# C8T6.net
KiCad netlist of a schematic drawn in Altium Designer
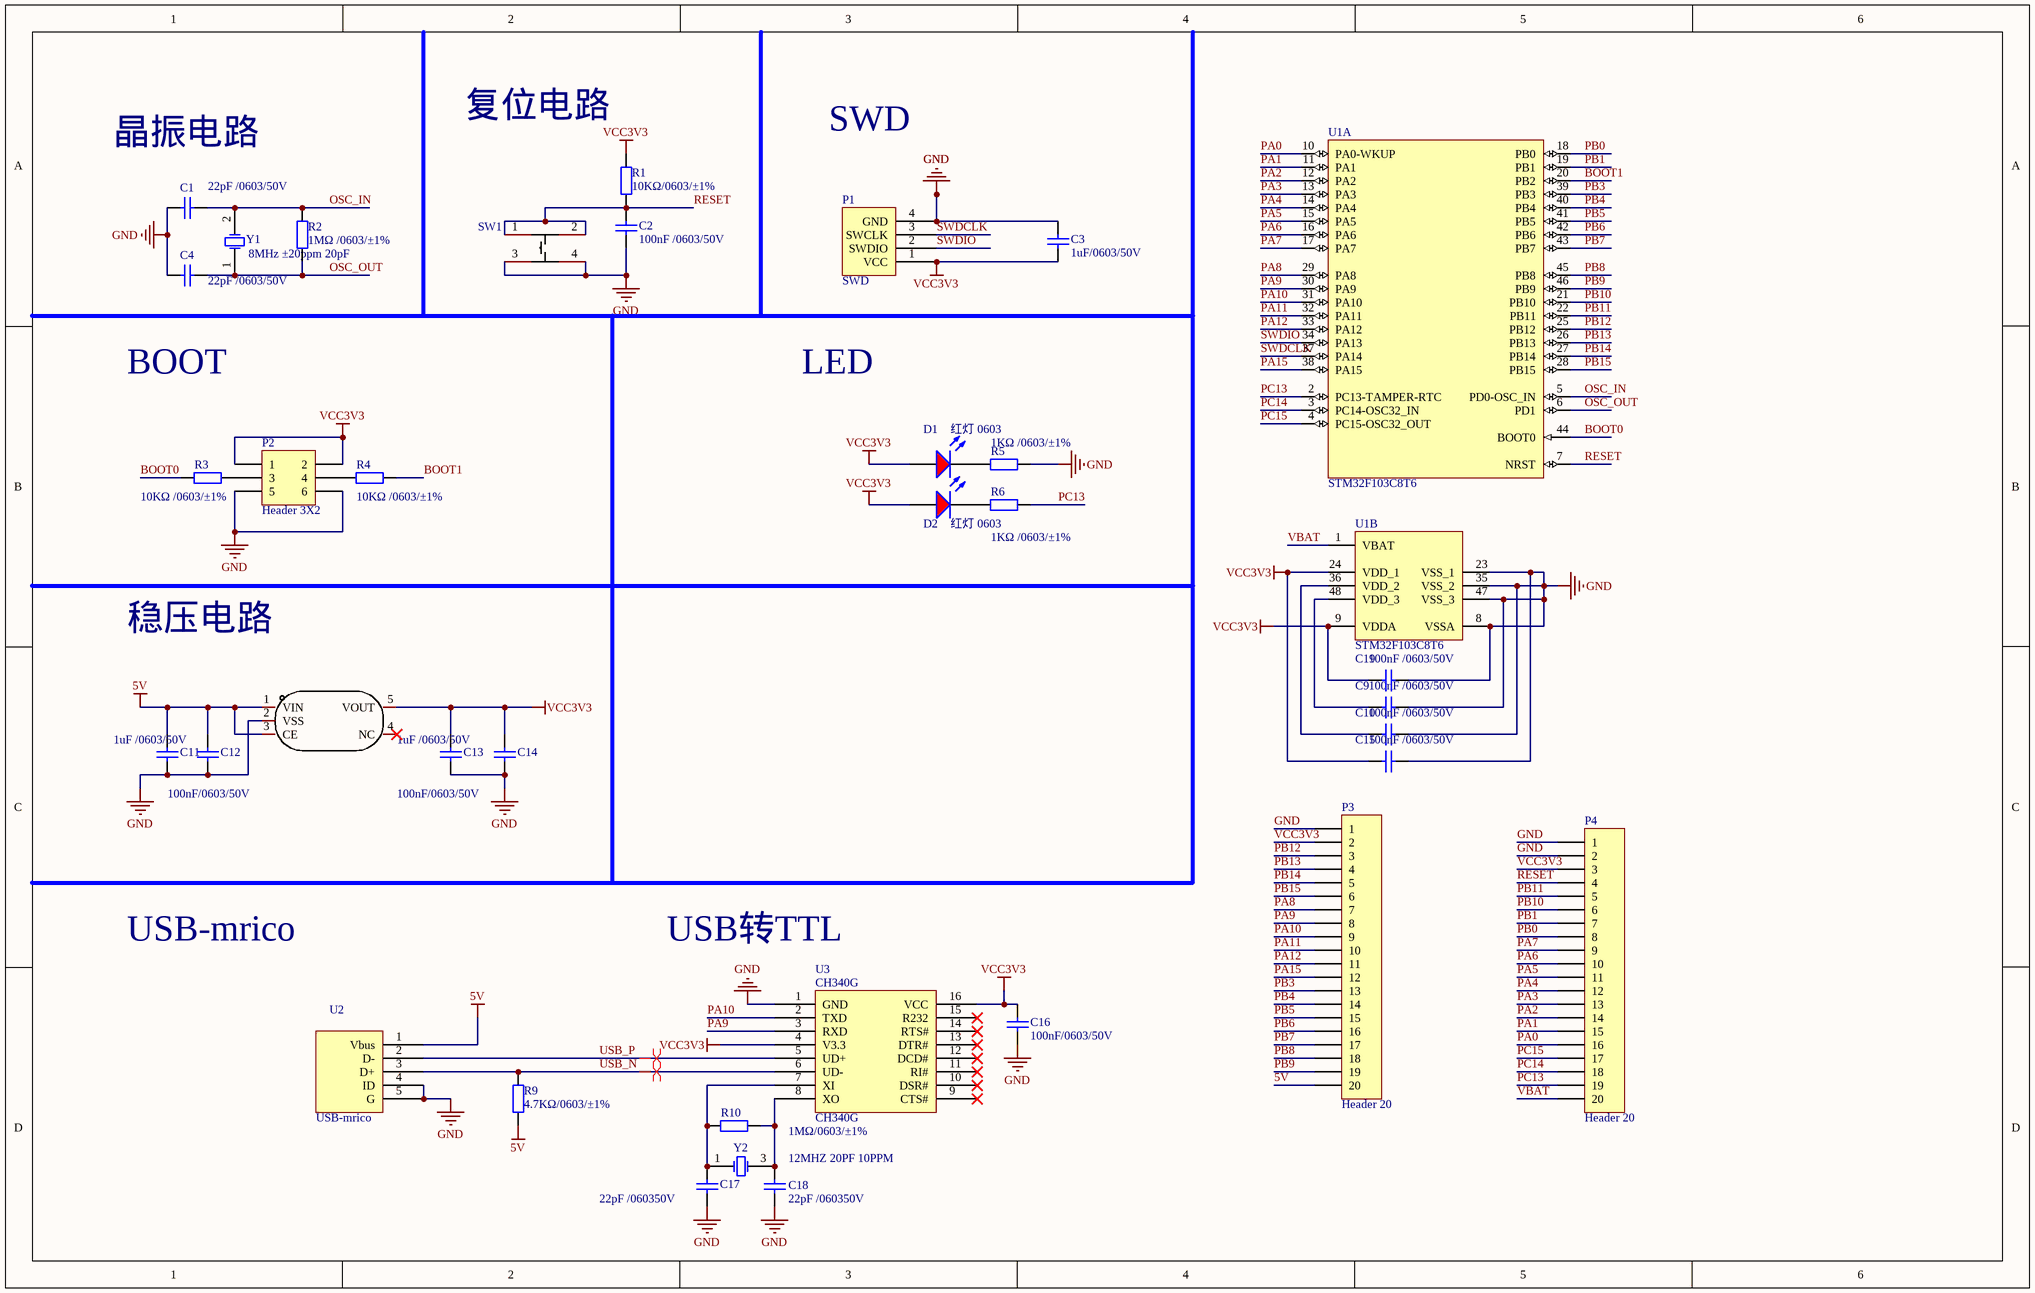
[diagram p0: C8T6.SchDoc]

(export (version "E")
  (design (tool "Eeschema 10.0.6"))
  (components
    (comp (ref "C1")
      (value "22pF /0603/50V")
      (footprint "0603_C")
      (description "贴片电容")
      (libsource (lib "C8T6") (part "0603 22pF (220) 5% 50V"))
    )
    (comp (ref "C2")
      (value "100nF /0603/50V")
      (footprint "0603_C")
      (description "贴片电容")
      (libsource (lib "C8T6") (part "0603 100nF (104) 10% 50V"))
    )
    (comp (ref "C3")
      (value "1uF/0603/50V")
      (footprint "0603_C")
      (description "贴片电容")
      (libsource (lib "C8T6") (part "0603 1uF (105) 10% 50V"))
    )
    (comp (ref "C4")
      (value "22pF /0603/50V")
      (footprint "0603_C")
      (description "贴片电容")
      (libsource (lib "C8T6") (part "0603 22pF (220) 5% 50V"))
    )
    (comp (ref "C9")
      (value "100nF /0603/50V")
      (footprint "0603_C")
      (description "贴片电容")
      (libsource (lib "C8T6") (part "0603 100nF (104) 10% 50V"))
    )
    (comp (ref "C10")
      (value "100nF /0603/50V")
      (footprint "0603_C")
      (description "贴片电容")
      (libsource (lib "C8T6") (part "0603 100nF (104) 10% 50V"))
    )
    (comp (ref "C11")
      (value "1uF /0603/50V")
      (footprint "0603_C")
      (description "贴片电容")
      (libsource (lib "C8T6") (part "0603 1uF (105) 10% 50V"))
    )
    (comp (ref "C12")
      (value "100nF/0603/50V")
      (footprint "0603_C")
      (description "贴片电容")
      (libsource (lib "C8T6") (part "0603 100nF (104) 10% 50V"))
    )
    (comp (ref "C13")
      (value "1uF /0603/50V")
      (footprint "0603_C")
      (description "贴片电容")
      (libsource (lib "C8T6") (part "0603 1uF (105) 10% 50V"))
    )
    (comp (ref "C14")
      (value "100nF/0603/50V")
      (footprint "0603_C")
      (description "贴片电容")
      (libsource (lib "C8T6") (part "0603 100nF (104) 10% 50V"))
    )
    (comp (ref "C15")
      (value "100nF /0603/50V")
      (footprint "0603_C")
      (description "贴片电容")
      (libsource (lib "C8T6") (part "0603 100nF (104) 10% 50V"))
    )
    (comp (ref "C16")
      (value "100nF/0603/50V")
      (footprint "0603_C")
      (description "贴片电容")
      (libsource (lib "C8T6") (part "0603 100nF (104) 10% 50V"))
    )
    (comp (ref "C17")
      (value "22pF /060350V")
      (footprint "0603_C")
      (description "贴片电容")
      (libsource (lib "C8T6") (part "0603 22pF (220) 5% 50V"))
    )
    (comp (ref "C18")
      (value "22pF /060350V")
      (footprint "0603_C")
      (description "贴片电容")
      (libsource (lib "C8T6") (part "0603 22pF (220) 5% 50V"))
    )
    (comp (ref "C19")
      (value "100nF /0603/50V")
      (footprint "0603_C")
      (description "贴片电容")
      (libsource (lib "C8T6") (part "0603 100nF (104) 10% 50V"))
    )
    (comp (ref "D1")
      (value "红灯 0603")
      (footprint "0603_LED_S1")
      (description "发光二极管")
      (libsource (lib "C8T6") (part "0603 红灯"))
    )
    (comp (ref "D2")
      (value "红灯 0603")
      (footprint "0603_LED_S1")
      (description "发光二极管")
      (libsource (lib "C8T6") (part "0603 红灯"))
    )
    (comp (ref "LDO1")
      (value "ME6211C33M5G-N")
      (footprint "SOT-23-5_L3.0-W1.7-P0.95-LS2.8-BL")
      (fields (field (name "MANUFACTURER") "MICRONE(南京微盟)"))
      (libsource (lib "altium-import") (part "root_0_ME6211C33M5G-N_"))
    )
    (comp (ref "P1") (value "SWD") (footprint "HDR4x1") (libsource (lib "系统板原理图库") (part "SWD")))
    (comp (ref "P2")
      (value "Header 3X2")
      (footprint "HDR2X3")
      (description "Header, 3-Pin, Dual row")
      (fields (field (name "PUBLISHER") "Altium Limited"))
      (libsource (lib "系统板原理图库") (part "Header 3X2"))
    )
    (comp (ref "P3")
      (value "Header 20")
      (footprint "HDR1X20")
      (description "Header, 20-Pin")
      (fields (field (name "PUBLISHER") "Altium Limited"))
      (libsource (lib "C8T6") (part "Header 20"))
    )
    (comp (ref "P4")
      (value "Header 20")
      (footprint "HDR1X20")
      (description "Header, 20-Pin")
      (fields (field (name "PUBLISHER") "Altium Limited"))
      (libsource (lib "C8T6") (part "Header 20"))
    )
    (comp (ref "R1")
      (value "10KΩ/0603/±1%")
      (footprint "0603_R")
      (description "贴片电阻")
      (libsource (lib "C8T6") (part "0603 10KΩ (1002) 1%_1"))
    )
    (comp (ref "R2")
      (value "1MΩ /0603/±1%")
      (footprint "0603_R")
      (description "贴片电阻")
      (libsource (lib "") (part "0603 1MΩ (1004) 1%_1"))
    )
    (comp (ref "R3")
      (value "10KΩ /0603/±1%")
      (footprint "0603_R")
      (description "贴片电阻")
      (libsource (lib "") (part "0603 10KΩ (1002) 1%_1_1"))
    )
    (comp (ref "R4")
      (value "10KΩ /0603/±1%")
      (footprint "0603_R")
      (description "贴片电阻")
      (libsource (lib "") (part "0603 10KΩ (1002) 1%_1_1"))
    )
    (comp (ref "R5")
      (value "1KΩ /0603/±1%")
      (footprint "0603_R")
      (description "贴片电阻")
      (libsource (lib "") (part "0603 10KΩ (1002) 1%_1_1"))
    )
    (comp (ref "R6")
      (value "1KΩ /0603/±1%")
      (footprint "0603_R")
      (description "贴片电阻")
      (libsource (lib "") (part "0603 10KΩ (1002) 1%_1_1"))
    )
    (comp (ref "R9")
      (value "4.7KΩ/0603/±1%")
      (footprint "0603_R")
      (description "贴片电阻")
      (libsource (lib "C8T6") (part "0603 4.7KΩ (4701) 1%"))
    )
    (comp (ref "R10")
      (value "1MΩ/0603/±1%")
      (footprint "0603_R")
      (description "贴片电阻")
      (libsource (lib "C8T6") (part "0603 1MΩ (1004) 1%"))
    )
    (comp (ref "SW1")
      (value "KEY_SMD_4P")
      (footprint "SW-SMD_4P-L4.2-W3.3-P2.15-LS5.1 - duplicate")
      (libsource (lib "系统板原理图库") (part "KEY_SMD_4P"))
    )
    (comp (ref "U1")
      (value "STM32F103C8T6")
      (footprint "LQFP-48_7x7x05P")
      (description "ARM")
      (libsource (lib "C8T6") (part "STM32F103C8T6"))
    )
    (comp (ref "U2") (value "USB-mrico") (footprint "Micro_USB") (libsource (lib "系统板原理图库") (part "usb-STM")))
    (comp (ref "U3")
      (value "CH340G")
      (footprint "SOIC-16_150mil")
      (description "USB")
      (libsource (lib "C8T6") (part "CH340G_[C14267]"))
    )
    (comp (ref "Y1")
      (value "8MHz ±20ppm 20pF")
      (footprint "SMD-5032_2P")
      (description "贴片晶振")
      (libsource (lib "C8T6") (part "SMD-5032_2P 8MHz 20ppm 20pF"))
    )
    (comp (ref "Y2")
      (value "12MHZ 20PF 10PPM")
      (footprint "SMD-3225_4P")
      (description "贴片晶振")
      (libsource (lib "C8T6") (part "SMD-3225_4P  12MHZ 20PF 10PPM"))
    )
  )
  (nets
    (net (code "1") (name "/BOOT0") (class "Default")
      (node (ref "R3") (pin "1") (pinfunction "1_1") (pintype "passive"))
      (node (ref "U1") (pin "44") (pinfunction "BOOT0_44") (pintype "input"))
    )
    (net (code "2") (name "/BOOT1") (class "Default")
      (node (ref "R4") (pin "2") (pinfunction "2_2") (pintype "passive"))
      (node (ref "U1") (pin "20") (pinfunction "PB2_20") (pintype "bidirectional"))
    )
    (net (code "3") (name "/OSC_IN") (class "Default")
      (node (ref "C1") (pin "2") (pinfunction "2_2") (pintype "passive"))
      (node (ref "R2") (pin "2") (pinfunction "2_2") (pintype "passive"))
      (node (ref "U1") (pin "5") (pinfunction "PD0-OSC_IN_5") (pintype "bidirectional"))
      (node (ref "Y1") (pin "2") (pinfunction "OSC2_2") (pintype "passive"))
    )
    (net (code "4") (name "/OSC_OUT") (class "Default")
      (node (ref "C4") (pin "2") (pinfunction "2_2") (pintype "passive"))
      (node (ref "R2") (pin "1") (pinfunction "1_1") (pintype "passive"))
      (node (ref "U1") (pin "6") (pinfunction "PD1_6") (pintype "bidirectional"))
      (node (ref "Y1") (pin "1") (pinfunction "OSC1_1") (pintype "passive"))
    )
    (net (code "5") (name "/PA0") (class "Default")
      (node (ref "P4") (pin "16") (pinfunction "16_16") (pintype "passive"))
      (node (ref "U1") (pin "10") (pinfunction "PA0-WKUP_10") (pintype "bidirectional"))
    )
    (net (code "6") (name "/PA1") (class "Default")
      (node (ref "P4") (pin "15") (pinfunction "15_15") (pintype "passive"))
      (node (ref "U1") (pin "11") (pinfunction "PA1_11") (pintype "bidirectional"))
    )
    (net (code "7") (name "/PA2") (class "Default")
      (node (ref "P4") (pin "14") (pinfunction "14_14") (pintype "passive"))
      (node (ref "U1") (pin "12") (pinfunction "PA2_12") (pintype "bidirectional"))
    )
    (net (code "8") (name "/PA3") (class "Default")
      (node (ref "P4") (pin "13") (pinfunction "13_13") (pintype "passive"))
      (node (ref "U1") (pin "13") (pinfunction "PA3_13") (pintype "bidirectional"))
    )
    (net (code "9") (name "/PA4") (class "Default")
      (node (ref "P4") (pin "12") (pinfunction "12_12") (pintype "passive"))
      (node (ref "U1") (pin "14") (pinfunction "PA4_14") (pintype "bidirectional"))
    )
    (net (code "10") (name "/PA5") (class "Default")
      (node (ref "P4") (pin "11") (pinfunction "11_11") (pintype "passive"))
      (node (ref "U1") (pin "15") (pinfunction "PA5_15") (pintype "bidirectional"))
    )
    (net (code "11") (name "/PA6") (class "Default")
      (node (ref "P4") (pin "10") (pinfunction "10_10") (pintype "passive"))
      (node (ref "U1") (pin "16") (pinfunction "PA6_16") (pintype "bidirectional"))
    )
    (net (code "12") (name "/PA7") (class "Default")
      (node (ref "P4") (pin "9") (pinfunction "9_9") (pintype "passive"))
      (node (ref "U1") (pin "17") (pinfunction "PA7_17") (pintype "bidirectional"))
    )
    (net (code "13") (name "/PA8") (class "Default")
      (node (ref "P3") (pin "7") (pinfunction "7_7") (pintype "passive"))
      (node (ref "U1") (pin "29") (pinfunction "PA8_29") (pintype "bidirectional"))
    )
    (net (code "14") (name "/PA9") (class "Default")
      (node (ref "P3") (pin "8") (pinfunction "8_8") (pintype "passive"))
      (node (ref "U1") (pin "30") (pinfunction "PA9_30") (pintype "bidirectional"))
      (node (ref "U3") (pin "3") (pinfunction "RXD_3") (pintype "passive"))
    )
    (net (code "15") (name "/PA10") (class "Default")
      (node (ref "P3") (pin "9") (pinfunction "9_9") (pintype "passive"))
      (node (ref "U1") (pin "31") (pinfunction "PA10_31") (pintype "bidirectional"))
      (node (ref "U3") (pin "2") (pinfunction "TXD_2") (pintype "passive"))
    )
    (net (code "16") (name "/PA11") (class "Default")
      (node (ref "P3") (pin "10") (pinfunction "10_10") (pintype "passive"))
      (node (ref "U1") (pin "32") (pinfunction "PA11_32") (pintype "bidirectional"))
    )
    (net (code "17") (name "/PA12") (class "Default")
      (node (ref "P3") (pin "11") (pinfunction "11_11") (pintype "passive"))
      (node (ref "U1") (pin "33") (pinfunction "PA12_33") (pintype "bidirectional"))
    )
    (net (code "18") (name "/PA15") (class "Default")
      (node (ref "P3") (pin "12") (pinfunction "12_12") (pintype "passive"))
      (node (ref "U1") (pin "38") (pinfunction "PA15_38") (pintype "bidirectional"))
    )
    (net (code "19") (name "/PB0") (class "Default")
      (node (ref "P4") (pin "8") (pinfunction "8_8") (pintype "passive"))
      (node (ref "U1") (pin "18") (pinfunction "PB0_18") (pintype "bidirectional"))
    )
    (net (code "20") (name "/PB1") (class "Default")
      (node (ref "P4") (pin "7") (pinfunction "7_7") (pintype "passive"))
      (node (ref "U1") (pin "19") (pinfunction "PB1_19") (pintype "bidirectional"))
    )
    (net (code "21") (name "/PB3") (class "Default")
      (node (ref "P3") (pin "13") (pinfunction "13_13") (pintype "passive"))
      (node (ref "U1") (pin "39") (pinfunction "PB3_39") (pintype "bidirectional"))
    )
    (net (code "22") (name "/PB4") (class "Default")
      (node (ref "P3") (pin "14") (pinfunction "14_14") (pintype "passive"))
      (node (ref "U1") (pin "40") (pinfunction "PB4_40") (pintype "bidirectional"))
    )
    (net (code "23") (name "/PB5") (class "Default")
      (node (ref "P3") (pin "15") (pinfunction "15_15") (pintype "passive"))
      (node (ref "U1") (pin "41") (pinfunction "PB5_41") (pintype "bidirectional"))
    )
    (net (code "24") (name "/PB6") (class "Default")
      (node (ref "P3") (pin "16") (pinfunction "16_16") (pintype "passive"))
      (node (ref "U1") (pin "42") (pinfunction "PB6_42") (pintype "bidirectional"))
    )
    (net (code "25") (name "/PB7") (class "Default")
      (node (ref "P3") (pin "17") (pinfunction "17_17") (pintype "passive"))
      (node (ref "U1") (pin "43") (pinfunction "PB7_43") (pintype "bidirectional"))
    )
    (net (code "26") (name "/PB8") (class "Default")
      (node (ref "P3") (pin "18") (pinfunction "18_18") (pintype "passive"))
      (node (ref "U1") (pin "45") (pinfunction "PB8_45") (pintype "bidirectional"))
    )
    (net (code "27") (name "/PB9") (class "Default")
      (node (ref "P3") (pin "19") (pinfunction "19_19") (pintype "passive"))
      (node (ref "U1") (pin "46") (pinfunction "PB9_46") (pintype "bidirectional"))
    )
    (net (code "28") (name "/PB10") (class "Default")
      (node (ref "P4") (pin "6") (pinfunction "6_6") (pintype "passive"))
      (node (ref "U1") (pin "21") (pinfunction "PB10_21") (pintype "bidirectional"))
    )
    (net (code "29") (name "/PB11") (class "Default")
      (node (ref "P4") (pin "5") (pinfunction "5_5") (pintype "passive"))
      (node (ref "U1") (pin "22") (pinfunction "PB11_22") (pintype "bidirectional"))
    )
    (net (code "30") (name "/PB12") (class "Default")
      (node (ref "P3") (pin "3") (pinfunction "3_3") (pintype "passive"))
      (node (ref "U1") (pin "25") (pinfunction "PB12_25") (pintype "bidirectional"))
    )
    (net (code "31") (name "/PB13") (class "Default")
      (node (ref "P3") (pin "4") (pinfunction "4_4") (pintype "passive"))
      (node (ref "U1") (pin "26") (pinfunction "PB13_26") (pintype "bidirectional"))
    )
    (net (code "32") (name "/PB14") (class "Default")
      (node (ref "P3") (pin "5") (pinfunction "5_5") (pintype "passive"))
      (node (ref "U1") (pin "27") (pinfunction "PB14_27") (pintype "bidirectional"))
    )
    (net (code "33") (name "/PB15") (class "Default")
      (node (ref "P3") (pin "6") (pinfunction "6_6") (pintype "passive"))
      (node (ref "U1") (pin "28") (pinfunction "PB15_28") (pintype "bidirectional"))
    )
    (net (code "34") (name "/PC13") (class "Default")
      (node (ref "P4") (pin "19") (pinfunction "19_19") (pintype "passive"))
      (node (ref "R6") (pin "2") (pinfunction "2_2") (pintype "passive"))
      (node (ref "U1") (pin "2") (pinfunction "PC13-TAMPER-RTC_2") (pintype "bidirectional"))
    )
    (net (code "35") (name "/PC14") (class "Default")
      (node (ref "P4") (pin "18") (pinfunction "18_18") (pintype "passive"))
      (node (ref "U1") (pin "3") (pinfunction "PC14-OSC32_IN_3") (pintype "bidirectional"))
    )
    (net (code "36") (name "/PC15") (class "Default")
      (node (ref "P4") (pin "17") (pinfunction "17_17") (pintype "passive"))
      (node (ref "U1") (pin "4") (pinfunction "PC15-OSC32_OUT_4") (pintype "bidirectional"))
    )
    (net (code "37") (name "/RESET") (class "Default")
      (node (ref "C2") (pin "2") (pinfunction "2_2") (pintype "passive"))
      (node (ref "P4") (pin "4") (pinfunction "4_4") (pintype "passive"))
      (node (ref "R1") (pin "1") (pinfunction "1_1") (pintype "passive"))
      (node (ref "SW1") (pin "1") (pinfunction "1_1") (pintype "passive"))
      (node (ref "SW1") (pin "2") (pinfunction "2_2") (pintype "passive"))
      (node (ref "U1") (pin "7") (pinfunction "NRST_7") (pintype "bidirectional"))
    )
    (net (code "38") (name "/SWDCLK") (class "Default")
      (node (ref "P1") (pin "3") (pinfunction "SWCLK_3") (pintype "passive"))
      (node (ref "U1") (pin "37") (pinfunction "PA14_37") (pintype "bidirectional"))
    )
    (net (code "39") (name "/SWDIO") (class "Default")
      (node (ref "P1") (pin "2") (pinfunction "SWDIO_2") (pintype "passive"))
      (node (ref "U1") (pin "34") (pinfunction "PA13_34") (pintype "bidirectional"))
    )
    (net (code "40") (name "/USB_N") (class "Default")
      (node (ref "R9") (pin "2") (pinfunction "2_2") (pintype "passive"))
      (node (ref "U2") (pin "3") (pinfunction "D+_3") (pintype "passive"))
      (node (ref "U3") (pin "6") (pinfunction "UD-_6") (pintype "passive"))
    )
    (net (code "41") (name "/USB_P") (class "Default")
      (node (ref "U2") (pin "2") (pinfunction "D-_2") (pintype "passive"))
      (node (ref "U3") (pin "5") (pinfunction "UD+_5") (pintype "passive"))
    )
    (net (code "42") (name "/VBAT") (class "Default")
      (node (ref "P4") (pin "20") (pinfunction "20_20") (pintype "passive"))
      (node (ref "U1") (pin "1") (pinfunction "VBAT_1") (pintype "power_in"))
    )
    (net (code "43") (name "5V") (class "Default")
      (node (ref "C11") (pin "2") (pinfunction "2_2") (pintype "passive"))
      (node (ref "C12") (pin "2") (pinfunction "2_2") (pintype "passive"))
      (node (ref "LDO1") (pin "1") (pinfunction "VIN_1") (pintype "passive"))
      (node (ref "LDO1") (pin "3") (pinfunction "CE_3") (pintype "passive"))
      (node (ref "P3") (pin "20") (pinfunction "20_20") (pintype "passive"))
      (node (ref "R9") (pin "1") (pinfunction "1_1") (pintype "passive"))
      (node (ref "U2") (pin "1") (pinfunction "Vbus_1") (pintype "passive"))
    )
    (net (code "44") (name "GND") (class "Default")
      (node (ref "C1") (pin "1") (pinfunction "1_1") (pintype "passive"))
      (node (ref "C10") (pin "2") (pinfunction "2_2") (pintype "passive"))
      (node (ref "C11") (pin "1") (pinfunction "1_1") (pintype "passive"))
      (node (ref "C12") (pin "1") (pinfunction "1_1") (pintype "passive"))
      (node (ref "C13") (pin "1") (pinfunction "1_1") (pintype "passive"))
      (node (ref "C14") (pin "1") (pinfunction "1_1") (pintype "passive"))
      (node (ref "C15") (pin "2") (pinfunction "2_2") (pintype "passive"))
      (node (ref "C16") (pin "2") (pinfunction "2_2") (pintype "passive"))
      (node (ref "C17") (pin "2") (pinfunction "2_2") (pintype "passive"))
      (node (ref "C18") (pin "2") (pinfunction "2_2") (pintype "passive"))
      (node (ref "C19") (pin "2") (pinfunction "2_2") (pintype "passive"))
      (node (ref "C2") (pin "1") (pinfunction "1_1") (pintype "passive"))
      (node (ref "C3") (pin "2") (pinfunction "2_2") (pintype "passive"))
      (node (ref "C4") (pin "1") (pinfunction "1_1") (pintype "passive"))
      (node (ref "C9") (pin "2") (pinfunction "2_2") (pintype "passive"))
      (node (ref "LDO1") (pin "2") (pinfunction "VSS_2") (pintype "passive"))
      (node (ref "P1") (pin "4") (pinfunction "GND_4") (pintype "passive"))
      (node (ref "P2") (pin "5") (pinfunction "5_5") (pintype "passive"))
      (node (ref "P2") (pin "6") (pinfunction "6_6") (pintype "passive"))
      (node (ref "P3") (pin "1") (pinfunction "1_1") (pintype "passive"))
      (node (ref "P4") (pin "1") (pinfunction "1_1") (pintype "passive"))
      (node (ref "P4") (pin "2") (pinfunction "2_2") (pintype "passive"))
      (node (ref "R5") (pin "2") (pinfunction "2_2") (pintype "passive"))
      (node (ref "SW1") (pin "3") (pinfunction "3_3") (pintype "passive"))
      (node (ref "SW1") (pin "4") (pinfunction "4_4") (pintype "passive"))
      (node (ref "U1") (pin "23") (pinfunction "VSS_1_23") (pintype "power_in"))
      (node (ref "U1") (pin "35") (pinfunction "VSS_2_35") (pintype "power_in"))
      (node (ref "U1") (pin "47") (pinfunction "VSS_3_47") (pintype "power_in"))
      (node (ref "U1") (pin "8") (pinfunction "VSSA_8") (pintype "power_in"))
      (node (ref "U2") (pin "4") (pinfunction "ID_4") (pintype "passive"))
      (node (ref "U2") (pin "5") (pinfunction "G_5") (pintype "passive"))
      (node (ref "U3") (pin "1") (pinfunction "GND_1") (pintype "passive"))
    )
    (net (code "45") (name "Net-(D1-PadK)") (class "Default")
      (node (ref "D1") (pin "K") (pinfunction "K_K") (pintype "passive"))
      (node (ref "R5") (pin "1") (pinfunction "1_1") (pintype "passive"))
    )
    (net (code "46") (name "Net-(D2-PadK)") (class "Default")
      (node (ref "D2") (pin "K") (pinfunction "K_K") (pintype "passive"))
      (node (ref "R6") (pin "1") (pinfunction "1_1") (pintype "passive"))
    )
    (net (code "47") (name "Net-(P2-Pad3)") (class "Default")
      (node (ref "P2") (pin "3") (pinfunction "3_3") (pintype "passive"))
      (node (ref "R3") (pin "2") (pinfunction "2_2") (pintype "passive"))
    )
    (net (code "48") (name "Net-(P2-Pad4)") (class "Default")
      (node (ref "P2") (pin "4") (pinfunction "4_4") (pintype "passive"))
      (node (ref "R4") (pin "1") (pinfunction "1_1") (pintype "passive"))
    )
    (net (code "49") (name "Net-(U1B-VDD_2)") (class "Default")
      (node (ref "C10") (pin "1") (pinfunction "1_1") (pintype "passive"))
      (node (ref "U1") (pin "36") (pinfunction "VDD_2_36") (pintype "power_in"))
    )
    (net (code "50") (name "Net-(U1B-VDD_3)") (class "Default")
      (node (ref "C9") (pin "1") (pinfunction "1_1") (pintype "passive"))
      (node (ref "U1") (pin "48") (pinfunction "VDD_3_48") (pintype "power_in"))
    )
    (net (code "51") (name "Net-(U3-XI)") (class "Default")
      (node (ref "C17") (pin "1") (pinfunction "1_1") (pintype "passive"))
      (node (ref "R10") (pin "1") (pinfunction "1_1") (pintype "passive"))
      (node (ref "U3") (pin "7") (pinfunction "XI_7") (pintype "passive"))
      (node (ref "Y2") (pin "1") (pinfunction "OSC1_1") (pintype "passive"))
    )
    (net (code "52") (name "Net-(U3-XO)") (class "Default")
      (node (ref "C18") (pin "1") (pinfunction "1_1") (pintype "passive"))
      (node (ref "R10") (pin "2") (pinfunction "2_2") (pintype "passive"))
      (node (ref "U3") (pin "8") (pinfunction "XO_8") (pintype "passive"))
      (node (ref "Y2") (pin "3") (pinfunction "OSC2_3") (pintype "passive"))
    )
    (net (code "53") (name "VCC3V3") (class "Default")
      (node (ref "C13") (pin "2") (pinfunction "2_2") (pintype "passive"))
      (node (ref "C14") (pin "2") (pinfunction "2_2") (pintype "passive"))
      (node (ref "C15") (pin "1") (pinfunction "1_1") (pintype "passive"))
      (node (ref "C16") (pin "1") (pinfunction "1_1") (pintype "passive"))
      (node (ref "C19") (pin "1") (pinfunction "1_1") (pintype "passive"))
      (node (ref "C3") (pin "1") (pinfunction "1_1") (pintype "passive"))
      (node (ref "D1") (pin "A") (pinfunction "A_A") (pintype "passive"))
      (node (ref "D2") (pin "A") (pinfunction "A_A") (pintype "passive"))
      (node (ref "LDO1") (pin "5") (pinfunction "VOUT_5") (pintype "passive"))
      (node (ref "P1") (pin "1") (pinfunction "VCC_1") (pintype "passive"))
      (node (ref "P2") (pin "1") (pinfunction "1_1") (pintype "passive"))
      (node (ref "P2") (pin "2") (pinfunction "2_2") (pintype "passive"))
      (node (ref "P3") (pin "2") (pinfunction "2_2") (pintype "passive"))
      (node (ref "P4") (pin "3") (pinfunction "3_3") (pintype "passive"))
      (node (ref "R1") (pin "2") (pinfunction "2_2") (pintype "passive"))
      (node (ref "U1") (pin "24") (pinfunction "VDD_1_24") (pintype "power_in"))
      (node (ref "U1") (pin "9") (pinfunction "VDDA_9") (pintype "power_in"))
      (node (ref "U3") (pin "16") (pinfunction "VCC_16") (pintype "passive"))
      (node (ref "U3") (pin "4") (pinfunction "V3.3_4") (pintype "passive"))
    )
    (net (code "54") (name "unconnected-(LDO1-NC-Pad4)") (class "Default")
      (node (ref "LDO1") (pin "4") (pinfunction "NC_4") (pintype "passive+no_connect"))
    )
    (net (code "55") (name "unconnected-(U3-CTS#-Pad9)") (class "Default")
      (node (ref "U3") (pin "9") (pinfunction "CTS#_9") (pintype "passive+no_connect"))
    )
    (net (code "56") (name "unconnected-(U3-DCD#-Pad12)") (class "Default")
      (node (ref "U3") (pin "12") (pinfunction "DCD#_12") (pintype "passive+no_connect"))
    )
    (net (code "57") (name "unconnected-(U3-DSR#-Pad10)") (class "Default")
      (node (ref "U3") (pin "10") (pinfunction "DSR#_10") (pintype "passive+no_connect"))
    )
    (net (code "58") (name "unconnected-(U3-DTR#-Pad13)") (class "Default")
      (node (ref "U3") (pin "13") (pinfunction "DTR#_13") (pintype "passive+no_connect"))
    )
    (net (code "59") (name "unconnected-(U3-R232-Pad15)") (class "Default")
      (node (ref "U3") (pin "15") (pinfunction "R232_15") (pintype "passive+no_connect"))
    )
    (net (code "60") (name "unconnected-(U3-RI#-Pad11)") (class "Default")
      (node (ref "U3") (pin "11") (pinfunction "RI#_11") (pintype "passive+no_connect"))
    )
    (net (code "61") (name "unconnected-(U3-RTS#-Pad14)") (class "Default")
      (node (ref "U3") (pin "14") (pinfunction "RTS#_14") (pintype "passive+no_connect"))
    )
  )
)
